# OSSI-1_OBC_3.net
KiCad netlist of a schematic drawn in Altium Designer
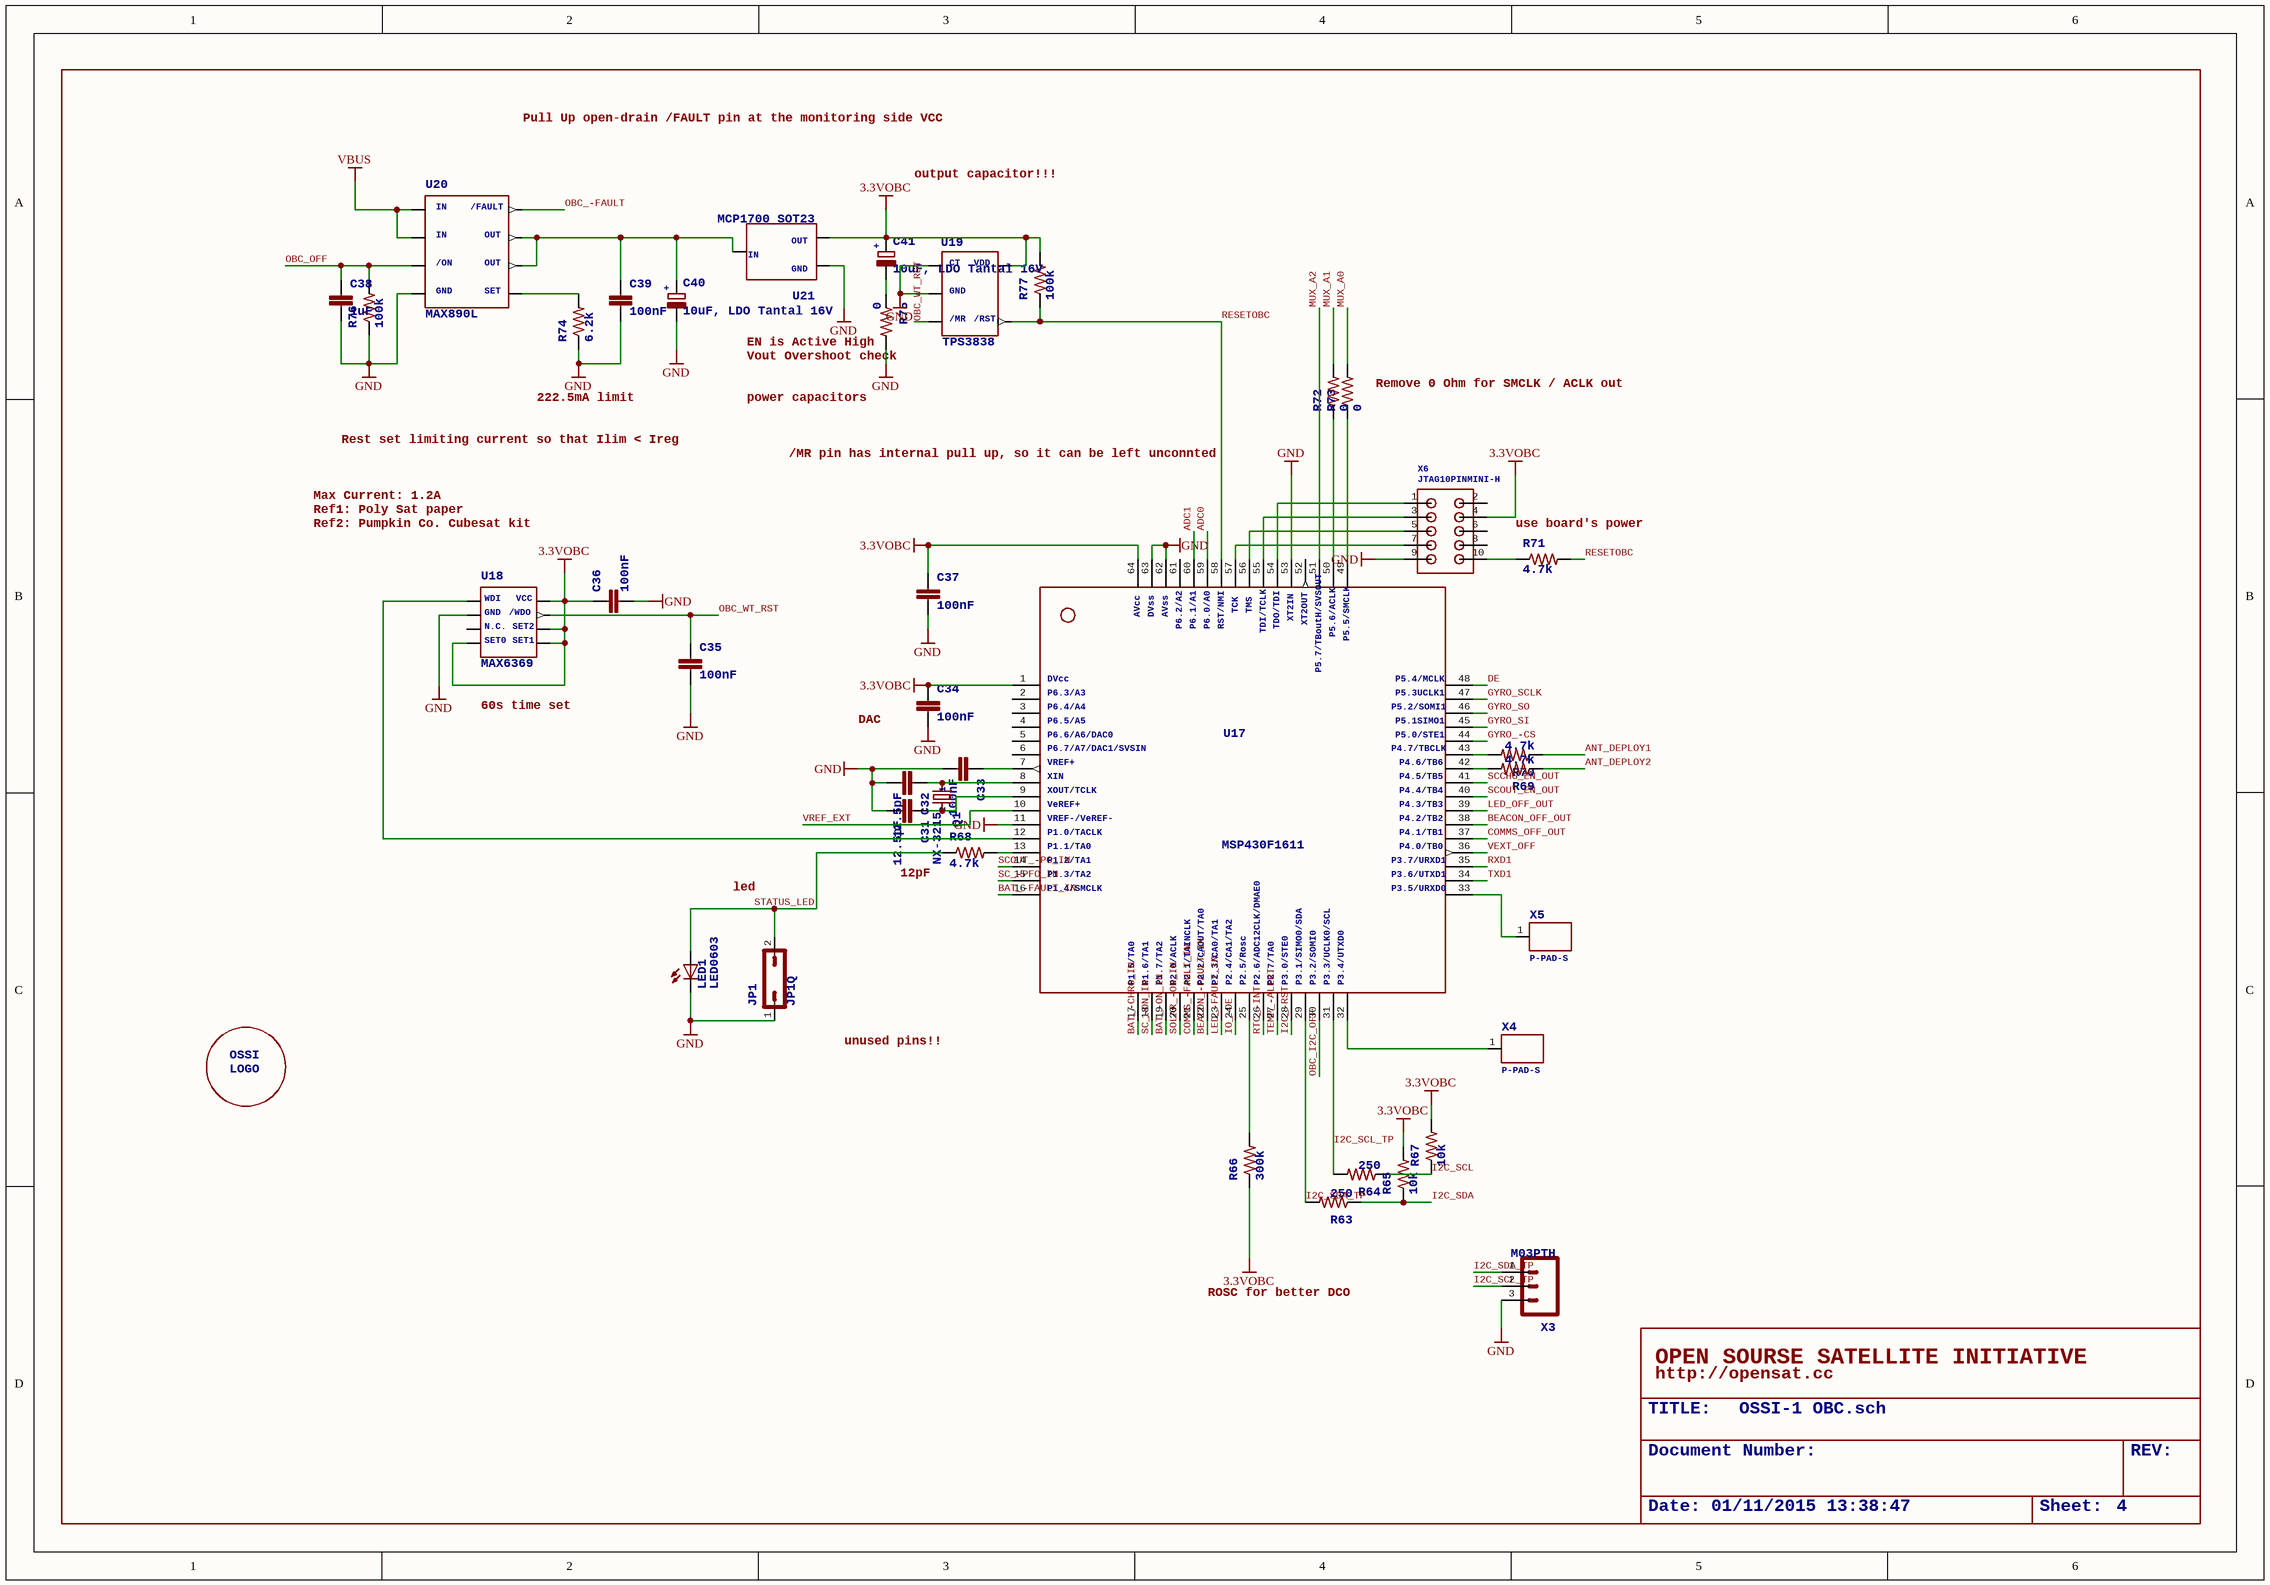
[diagram p0: OSSI-1 OBC_3.SchDoc]

(export (version "E")
  (design (tool "Eeschema 10.0.6"))
  (components
    (comp (ref "C31")
      (value "12.5pF")
      (footprint "C0603(1608)")
      (fields (field (name ">NAME") "C31") (field (name ">VALUE") "12.5pF"))
      (libsource (lib "") (part "C0603(1608)_1"))
    )
    (comp (ref "C32")
      (value "12.5pF")
      (footprint "C0603(1608)")
      (fields (field (name ">NAME") "C32") (field (name ">VALUE") "12.5pF"))
      (libsource (lib "") (part "C0603(1608)_1"))
    )
    (comp (ref "C33")
      (value "100nF")
      (footprint "C0603(1608)")
      (fields (field (name ">NAME") "C33") (field (name ">VALUE") "100nF"))
      (libsource (lib "") (part "C0603(1608)_1"))
    )
    (comp (ref "C34")
      (value "100nF")
      (footprint "C0603(1608)")
      (fields (field (name ">NAME") "C34") (field (name ">VALUE") "100nF"))
      (libsource (lib "") (part "C0603(1608)_2"))
    )
    (comp (ref "C35")
      (value "100nF")
      (footprint "C0603(1608)")
      (fields (field (name ">NAME") "C35") (field (name ">VALUE") "100nF"))
      (libsource (lib "") (part "C0603(1608)_2"))
    )
    (comp (ref "C36")
      (value "100nF")
      (footprint "C0603(1608)")
      (fields (field (name ">NAME") "C36") (field (name ">VALUE") "100nF"))
      (libsource (lib "OSSI") (part "C0603(1608)"))
    )
    (comp (ref "C37")
      (value "100nF")
      (footprint "C0603(1608)")
      (fields (field (name ">NAME") "C37") (field (name ">VALUE") "100nF"))
      (libsource (lib "") (part "C0603(1608)_2"))
    )
    (comp (ref "C38")
      (value "1uF")
      (footprint "C0603(1608)")
      (fields (field (name ">NAME") "C38") (field (name ">VALUE") "1uF"))
      (libsource (lib "") (part "C0603(1608)_2"))
    )
    (comp (ref "C39")
      (value "100nF")
      (footprint "C0603(1608)")
      (fields (field (name ">NAME") "C39") (field (name ">VALUE") "100nF"))
      (libsource (lib "") (part "C0603(1608)_2"))
    )
    (comp (ref "C40")
      (value "10uF, LDO Tantal 16V")
      (footprint "C1206(3216)-A")
      (fields
        (field (name ">NAME") "C40")
        (field (name "+") "+")
        (field (name ">VALUE") "10uF, LDO Tantal 16V")
      )
      (libsource (lib "OSSI") (part "C-TANTAL-A"))
    )
    (comp (ref "C41")
      (value "10uF, LDO Tantal 16V")
      (footprint "C1206(3216)-A")
      (fields
        (field (name ">NAME") "C41")
        (field (name "+") "+")
        (field (name ">VALUE") "10uF, LDO Tantal 16V")
      )
      (libsource (lib "OSSI") (part "C-TANTAL-A"))
    )
    (comp (ref "JP1")
      (value "JP1Q")
      (footprint "JP1")
      (description "<b>JUMPER</b>")
      (fields (field (name ">NAME") "JP1") (field (name ">VALUE") "JP1Q"))
      (libsource (lib "OSSI") (part "JP1Q"))
    )
    (comp (ref "LED1")
      (value "LED0603")
      (footprint "LED-0603")
      (fields (field (name ">NAME") "LED1") (field (name ">VALUE") "LED0603"))
      (libsource (lib "SparkFun") (part "LED0603"))
    )
    (comp (ref "Q1")
      (value "NX-3215")
      (footprint "NX-3215")
      (fields
        (field (name ">NAME") "Q1")
        (field (name ">VALUE") "NX-3215")
        (field (name "1") "1")
        (field (name "2") "2")
      )
      (libsource (lib "OSSI") (part "NX-3215"))
    )
    (comp (ref "R63")
      (value "250")
      (footprint "R0603(1608)")
      (fields (field (name ">NAME") "R63") (field (name ">VALUE") "250"))
      (libsource (lib "OSSI") (part "R0603(1608)"))
    )
    (comp (ref "R64")
      (value "250")
      (footprint "R0603(1608)")
      (fields (field (name ">NAME") "R64") (field (name ">VALUE") "250"))
      (libsource (lib "OSSI") (part "R0603(1608)"))
    )
    (comp (ref "R65")
      (value "10k")
      (footprint "R0603(1608)")
      (fields (field (name ">NAME") "R65") (field (name ">VALUE") "10k"))
      (libsource (lib "OSSI") (part "R0603(1608)"))
    )
    (comp (ref "R66")
      (value "300k")
      (footprint "R0603(1608)")
      (fields (field (name ">NAME") "R66") (field (name ">VALUE") "300k"))
      (libsource (lib "OSSI") (part "R0603(1608)"))
    )
    (comp (ref "R67")
      (value "10k")
      (footprint "R0603(1608)")
      (fields (field (name ">NAME") "R67") (field (name ">VALUE") "10k"))
      (libsource (lib "OSSI") (part "R0603(1608)"))
    )
    (comp (ref "R68")
      (value "4.7k")
      (footprint "R0603(1608)")
      (fields (field (name ">NAME") "R68") (field (name ">VALUE") "4.7k"))
      (libsource (lib "OSSI") (part "R0603(1608)"))
    )
    (comp (ref "R69")
      (value "4.7k")
      (footprint "R0603(1608)")
      (fields (field (name ">NAME") "R69") (field (name ">VALUE") "4.7k"))
      (libsource (lib "OSSI") (part "R0603(1608)"))
    )
    (comp (ref "R70")
      (value "4.7k")
      (footprint "R0603(1608)")
      (fields (field (name ">NAME") "R70") (field (name ">VALUE") "4.7k"))
      (libsource (lib "OSSI") (part "R0603(1608)"))
    )
    (comp (ref "R71")
      (value "4.7k")
      (footprint "R0603(1608)")
      (fields (field (name ">NAME") "R71") (field (name ">VALUE") "4.7k"))
      (libsource (lib "OSSI") (part "R0603(1608)"))
    )
    (comp (ref "R72")
      (value "0")
      (footprint "R0603(1608)")
      (fields (field (name ">NAME") "R72") (field (name ">VALUE") "0"))
      (libsource (lib "OSSI") (part "R0603(1608)"))
    )
    (comp (ref "R73")
      (value "0")
      (footprint "R0603(1608)")
      (fields (field (name ">NAME") "R73") (field (name ">VALUE") "0"))
      (libsource (lib "OSSI") (part "R0603(1608)"))
    )
    (comp (ref "R74")
      (value "6.2k")
      (footprint "R0603(1608)")
      (fields (field (name ">NAME") "R74") (field (name ">VALUE") "6.2k"))
      (libsource (lib "OSSI") (part "R0603(1608)"))
    )
    (comp (ref "R75")
      (value "0")
      (footprint "R0603(1608)")
      (fields (field (name ">NAME") "R75") (field (name ">VALUE") "0"))
      (libsource (lib "OSSI") (part "R0603(1608)"))
    )
    (comp (ref "R76")
      (value "100k")
      (footprint "R0603(1608)")
      (fields (field (name ">NAME") "R76") (field (name ">VALUE") "100k"))
      (libsource (lib "OSSI") (part "R0603(1608)"))
    )
    (comp (ref "R77")
      (value "100k")
      (footprint "R0603(1608)")
      (fields (field (name ">NAME") "R77") (field (name ">VALUE") "100k"))
      (libsource (lib "OSSI") (part "R0603(1608)"))
    )
    (comp (ref "U$1")
      (value "OSSILOGORECT")
      (footprint "OSSILOGORECT1005")
      (fields (field (name "OSSI") "OSSI") (field (name "LOGO") "LOGO"))
      (libsource (lib "OSSI") (part "OSSILOGORECT"))
    )
    (comp (ref "U17")
      (value "MSP430F1611")
      (footprint "PM/PAG64")
      (description "<b>MSP430F1611</b>")
      (fields
        (field (name "AVCC") "AVcc")
        (field (name "DVSS") "DVss")
        (field (name "AVSS") "AVss")
        (field (name "P6.2/A2") "P6.2/A2")
        (field (name "P6.1/A1") "P6.1/A1")
        (field (name "P6.0/A0") "P6.0/A0")
        (field (name "RST/NMI") "RST/NMI")
        (field (name "TCK") "TCK")
        (field (name "TMS") "TMS")
        (field (name "TDI/TCLK") "TDI/TCLK")
        (field (name "TDO/TDI") "TDO/TDI")
        (field (name "XT2IN") "XT2IN")
        (field (name "XT2OUT") "XT2OUT")
        (field (name "P5.7/TBOUTH/SVSOUT") "P5.7/TBoutH/SVSOUT")
        (field (name "P5.6/ACLK") "P5.6/ACLK")
        (field (name "P5.5/SMCLK") "P5.5/SMCLK")
        (field (name "DVCC") "DVcc")
        (field (name "P6.3/A3") "P6.3/A3")
        (field (name "P6.4/A4") "P6.4/A4")
        (field (name "P6.5/A5") "P6.5/A5")
        (field (name "P6.6/A6/DAC0") "P6.6/A6/DAC0")
        (field (name "P6.7/A7/DAC1/SVSIN") "P6.7/A7/DAC1/SVSIN")
        (field (name "VREF+") "VREF+")
        (field (name "XIN") "XIN")
        (field (name "XOUT/TCLK") "XOUT/TCLK")
        (field (name "VEREF+") "VeREF+")
        (field (name "VREF-/VEREF-") "VREF-/VeREF-")
        (field (name "P1.0/TACLK") "P1.0/TACLK")
        (field (name "P1.1/TA0") "P1.1/TA0")
        (field (name "P1.2/TA1") "P1.2/TA1")
        (field (name "P1.3/TA2") "P1.3/TA2")
        (field (name "P1.4/SMCLK") "P1.4/SMCLK")
        (field (name "P1.5/TA0") "P1.5/TA0")
        (field (name "P1.6/TA1") "P1.6/TA1")
        (field (name "P1.7/TA2") "P1.7/TA2")
        (field (name "P2.0/ACLK") "P2.0/ACLK")
        (field (name "P2.1/TAINCLK") "P2.1/TAINCLK")
        (field (name "P2.2/CAOUT/TA0") "P2.2/CAOUT/TA0")
        (field (name "P2.3/CA0/TA1") "P2.3/CA0/TA1")
        (field (name "P2.4/CA1/TA2") "P2.4/CA1/TA2")
        (field (name "P2.5/ROSC") "P2.5/Rosc")
        (field (name "P2.6/ADC12CLK/DMAE0") "P2.6/ADC12CLK/DMAE0")
        (field (name "P2.7/TA0") "P2.7/TA0")
        (field (name "P3.0/STE0") "P3.0/STE0")
        (field (name "P3.1/SIMO0/SDA") "P3.1/SIMO0/SDA")
        (field (name "P3.2/SOMI0") "P3.2/SOMI0")
        (field (name "P3.3/UCLK0/SCL") "P3.3/UCLK0/SCL")
        (field (name "P3.4/UTXD0") "P3.4/UTXD0")
        (field (name "P5.4/MCLK") "P5.4/MCLK")
        (field (name "P5.3UCLK1") "P5.3UCLK1")
        (field (name "P5.2/SOMI1") "P5.2/SOMI1")
        (field (name "P5.1SIMO1") "P5.1SIMO1")
        (field (name "P5.0/STE1") "P5.0/STE1")
        (field (name "P4.7/TBCLK") "P4.7/TBCLK")
        (field (name "P4.6/TB6") "P4.6/TB6")
        (field (name "P4.5/TB5") "P4.5/TB5")
        (field (name "P4.4/TB4") "P4.4/TB4")
        (field (name "P4.3/TB3") "P4.3/TB3")
        (field (name "P4.2/TB2") "P4.2/TB2")
        (field (name "P4.1/TB1") "P4.1/TB1")
        (field (name "P4.0/TB0") "P4.0/TB0")
        (field (name "P3.7/URXD1") "P3.7/URXD1")
        (field (name "P3.6/UTXD1") "P3.6/UTXD1")
        (field (name "P3.5/URXD0") "P3.5/URXD0")
        (field (name ">VALUE") "MSP430F1611")
        (field (name ">NAME") "U17")
      )
      (libsource (lib "OSSI") (part "MSP430F1611"))
    )
    (comp (ref "U18")
      (value "MAX6369")
      (footprint "SOT23-8")
      (fields
        (field (name "WDI") "WDI")
        (field (name "GND") "GND")
        (field (name "N.C.") "N.C.")
        (field (name "SET0") "SET0")
        (field (name "SET1") "SET1")
        (field (name "SET2") "SET2")
        (field (name "/WDO") "/WDO")
        (field (name "VCC") "VCC")
        (field (name ">NAME") "U18")
        (field (name ">VALUE") "MAX6369")
      )
      (libsource (lib "OSSI") (part "MAX6369"))
    )
    (comp (ref "U19")
      (value "TPS3838")
      (footprint "SOT23-5DBV")
      (fields
        (field (name ">NAME") "U19")
        (field (name ">VALUE") "TPS3838")
        (field (name "CT") "CT")
        (field (name "/MR") "/MR")
        (field (name "GND") "GND")
        (field (name "VDD") "VDD")
        (field (name "/RST") "/RST")
      )
      (libsource (lib "OSSI") (part "TPS3838"))
    )
    (comp (ref "U20")
      (value "MAX890L")
      (footprint "SO8")
      (fields
        (field (name "IN") "IN")
        (field (name "IN_1") "IN")
        (field (name "/ON") "/ON")
        (field (name "GND") "GND")
        (field (name "SET") "SET")
        (field (name "OUT") "OUT")
        (field (name "OUT_1") "OUT")
        (field (name "/FAULT") "/FAULT")
        (field (name ">NAME") "U20")
        (field (name ">VALUE") "MAX890L")
      )
      (libsource (lib "OSSI") (part "MAX890L"))
    )
    (comp (ref "U21")
      (value "MCP1700_SOT23")
      (footprint "SOT23")
      (description "MCP1700 LDO from Microchips")
      (fields
        (field (name ">NAME") "U21")
        (field (name ">VALUE") "MCP1700_SOT23")
        (field (name "IN") "IN")
        (field (name "GND") "GND")
        (field (name "OUT") "OUT")
      )
      (libsource (lib "OSSI") (part "MCP1700_SOT23"))
    )
    (comp (ref "X3")
      (value "M03PTH")
      (footprint "1X03")
      (fields (field (name ">VALUE") "M03PTH") (field (name ">NAME") "X3"))
      (libsource (lib "OSSI") (part "M03PTH"))
    )
    (comp (ref "X4")
      (value "P-PAD-S")
      (footprint "P-PAD-S")
      (fields (field (name ">NAME") "X4") (field (name ">VALUE") "P-PAD-S"))
      (libsource (lib "OSSI") (part "P-PAD-S"))
    )
    (comp (ref "X5")
      (value "P-PAD-S")
      (footprint "P-PAD-S")
      (fields (field (name ">NAME") "X5") (field (name ">VALUE") "P-PAD-S"))
      (libsource (lib "OSSI") (part "P-PAD-S"))
    )
    (comp (ref "X6")
      (value "JTAG10PINMINI-H")
      (footprint "M50-3200545")
      (fields (field (name ">NAME") "X6") (field (name ">VALUE") "JTAG10PINMINI-H"))
      (libsource (lib "OSSI") (part "JTAG10PINMINI-H"))
    )
  )
  (nets
    (net (code "1") (name "/ADC0") (class "Default")
      (node (ref "U17") (pin "59") (pinfunction "59_59") (pintype "passive"))
    )
    (net (code "2") (name "/ADC1") (class "Default")
      (node (ref "U17") (pin "60") (pinfunction "60_60") (pintype "passive"))
    )
    (net (code "3") (name "/ANT_DEPLOY1") (class "Default")
      (node (ref "R70") (pin "1") (pinfunction "1_1") (pintype "passive"))
    )
    (net (code "4") (name "/ANT_DEPLOY2") (class "Default")
      (node (ref "R69") (pin "1") (pinfunction "1_1") (pintype "passive"))
    )
    (net (code "5") (name "/BAT_-CHRG_IN") (class "Default")
      (node (ref "U17") (pin "17") (pinfunction "17_17") (pintype "passive"))
    )
    (net (code "6") (name "/BAT_-FAULT_IN") (class "Default")
      (node (ref "U17") (pin "16") (pinfunction "16_16") (pintype "passive"))
    )
    (net (code "7") (name "/BAT_-ON_IN") (class "Default")
      (node (ref "U17") (pin "19") (pinfunction "19_19") (pintype "passive"))
    )
    (net (code "8") (name "/BEACON_-FAULT_IN") (class "Default")
      (node (ref "U17") (pin "22") (pinfunction "22_22") (pintype "passive"))
    )
    (net (code "9") (name "/BEACON_OFF_OUT") (class "Default")
      (node (ref "U17") (pin "38") (pinfunction "38_38") (pintype "passive"))
    )
    (net (code "10") (name "/COMMS_-FAULT_IN") (class "Default")
      (node (ref "U17") (pin "21") (pinfunction "21_21") (pintype "passive"))
    )
    (net (code "11") (name "/COMMS_OFF_OUT") (class "Default")
      (node (ref "U17") (pin "37") (pinfunction "37_37") (pintype "passive"))
    )
    (net (code "12") (name "/DE") (class "Default")
      (node (ref "U17") (pin "48") (pinfunction "48_48") (pintype "passive"))
    )
    (net (code "13") (name "/GYRO_-CS") (class "Default")
      (node (ref "U17") (pin "44") (pinfunction "44_44") (pintype "passive"))
    )
    (net (code "14") (name "/GYRO_SCLK") (class "Default")
      (node (ref "U17") (pin "47") (pinfunction "47_47") (pintype "passive"))
    )
    (net (code "15") (name "/GYRO_SI") (class "Default")
      (node (ref "U17") (pin "45") (pinfunction "45_45") (pintype "passive"))
    )
    (net (code "16") (name "/GYRO_SO") (class "Default")
      (node (ref "U17") (pin "46") (pinfunction "46_46") (pintype "passive"))
    )
    (net (code "17") (name "/I2C_-RST") (class "Default")
      (node (ref "U17") (pin "28") (pinfunction "28_28") (pintype "passive"))
    )
    (net (code "18") (name "/I2C_SCL") (class "Default")
      (node (ref "R64") (pin "1") (pinfunction "1_1") (pintype "passive"))
      (node (ref "R67") (pin "1") (pinfunction "1_1") (pintype "passive"))
    )
    (net (code "19") (name "/I2C_SCL_TP") (class "Default")
      (node (ref "R64") (pin "2") (pinfunction "2_2") (pintype "passive"))
      (node (ref "U17") (pin "31") (pinfunction "31_31") (pintype "passive"))
      (node (ref "X3") (pin "2") (pinfunction "2_2") (pintype "passive"))
    )
    (net (code "20") (name "/I2C_SDA") (class "Default")
      (node (ref "R63") (pin "1") (pinfunction "1_1") (pintype "passive"))
      (node (ref "R65") (pin "1") (pinfunction "1_1") (pintype "passive"))
    )
    (net (code "21") (name "/I2C_SDA_TP") (class "Default")
      (node (ref "R63") (pin "2") (pinfunction "2_2") (pintype "passive"))
      (node (ref "U17") (pin "29") (pinfunction "29_29") (pintype "passive"))
      (node (ref "X3") (pin "1") (pinfunction "1_1") (pintype "passive"))
    )
    (net (code "22") (name "/IO_-OE") (class "Default")
      (node (ref "U17") (pin "24") (pinfunction "24_24") (pintype "passive"))
    )
    (net (code "23") (name "/LED_-FAULT_IN") (class "Default")
      (node (ref "U17") (pin "23") (pinfunction "23_23") (pintype "passive"))
    )
    (net (code "24") (name "/LED_OFF_OUT") (class "Default")
      (node (ref "U17") (pin "39") (pinfunction "39_39") (pintype "passive"))
    )
    (net (code "25") (name "/MUX_A0") (class "Default")
      (node (ref "R73") (pin "2") (pinfunction "2_2") (pintype "passive"))
    )
    (net (code "26") (name "/MUX_A1") (class "Default")
      (node (ref "R72") (pin "2") (pinfunction "2_2") (pintype "passive"))
    )
    (net (code "27") (name "/MUX_A2") (class "Default")
      (node (ref "U17") (pin "51") (pinfunction "51_51") (pintype "passive"))
    )
    (net (code "28") (name "/OBC_-FAULT") (class "Default")
      (node (ref "U20") (pin "8") (pinfunction "P$8_8") (pintype "output"))
    )
    (net (code "29") (name "/OBC_I2C_OFF") (class "Default")
      (node (ref "U17") (pin "30") (pinfunction "30_30") (pintype "passive"))
    )
    (net (code "30") (name "/OBC_OFF") (class "Default")
      (node (ref "C38") (pin "1") (pinfunction "1_1") (pintype "passive"))
      (node (ref "R76") (pin "2") (pinfunction "2_2") (pintype "passive"))
      (node (ref "U20") (pin "3") (pinfunction "P$3_3") (pintype "passive"))
    )
    (net (code "31") (name "/OBC_WT_RST") (class "Default")
      (node (ref "C35") (pin "1") (pinfunction "1_1") (pintype "passive"))
      (node (ref "U18") (pin "7") (pinfunction "P$7_7") (pintype "output"))
      (node (ref "U19") (pin "3") (pinfunction "P$3_3") (pintype "passive"))
    )
    (net (code "32") (name "/RESETOBC") (class "Default")
      (node (ref "R71") (pin "2") (pinfunction "2_2") (pintype "passive"))
      (node (ref "R77") (pin "1") (pinfunction "1_1") (pintype "passive"))
      (node (ref "U17") (pin "58") (pinfunction "58_58") (pintype "passive"))
      (node (ref "U19") (pin "4") (pinfunction "P$4_4") (pintype "output"))
    )
    (net (code "33") (name "/RTC_-INT") (class "Default")
      (node (ref "U17") (pin "26") (pinfunction "26_26") (pintype "passive"))
    )
    (net (code "34") (name "/RXD1") (class "Default")
      (node (ref "U17") (pin "35") (pinfunction "35_35") (pintype "passive"))
    )
    (net (code "35") (name "/SCCHG_EN_OUT") (class "Default")
      (node (ref "U17") (pin "41") (pinfunction "41_41") (pintype "passive"))
    )
    (net (code "36") (name "/SCOUT_-PG_IN") (class "Default")
      (node (ref "U17") (pin "14") (pinfunction "14_14") (pintype "passive"))
    )
    (net (code "37") (name "/SCOUT_EN_OUT") (class "Default")
      (node (ref "U17") (pin "40") (pinfunction "40_40") (pintype "passive"))
    )
    (net (code "38") (name "/SC_-ON_IN") (class "Default")
      (node (ref "U17") (pin "18") (pinfunction "18_18") (pintype "passive"))
    )
    (net (code "39") (name "/SC_-PFO_IN") (class "Default")
      (node (ref "U17") (pin "15") (pinfunction "15_15") (pintype "passive"))
    )
    (net (code "40") (name "/SOLAR_-ON_IN") (class "Default")
      (node (ref "U17") (pin "20") (pinfunction "20_20") (pintype "passive"))
    )
    (net (code "41") (name "/STATUS_LED") (class "Default")
      (node (ref "JP1") (pin "2") (pinfunction "2_2") (pintype "passive"))
      (node (ref "LED1") (pin "A") (pinfunction "A_A") (pintype "passive"))
      (node (ref "R68") (pin "1") (pinfunction "1_1") (pintype "passive"))
    )
    (net (code "42") (name "/TEMP_-ALERT") (class "Default")
      (node (ref "U17") (pin "27") (pinfunction "27_27") (pintype "passive"))
    )
    (net (code "43") (name "/TXD1") (class "Default")
      (node (ref "U17") (pin "34") (pinfunction "34_34") (pintype "passive"))
    )
    (net (code "44") (name "/VEXT_OFF") (class "Default")
      (node (ref "U17") (pin "36") (pinfunction "36_36") (pintype "output"))
    )
    (net (code "45") (name "/VREF_EXT") (class "Default")
      (node (ref "U17") (pin "10") (pinfunction "10_10") (pintype "passive"))
    )
    (net (code "46") (name "3.3VOBC") (class "Default")
      (node (ref "C34") (pin "1") (pinfunction "1_1") (pintype "passive"))
      (node (ref "C36") (pin "1") (pinfunction "1_1") (pintype "passive"))
      (node (ref "C37") (pin "1") (pinfunction "1_1") (pintype "passive"))
      (node (ref "C41") (pin "1") (pinfunction "+_1") (pintype "passive"))
      (node (ref "R65") (pin "2") (pinfunction "2_2") (pintype "passive"))
      (node (ref "R66") (pin "1") (pinfunction "1_1") (pintype "passive"))
      (node (ref "R67") (pin "2") (pinfunction "2_2") (pintype "passive"))
      (node (ref "R77") (pin "2") (pinfunction "2_2") (pintype "passive"))
      (node (ref "U17") (pin "1") (pinfunction "1_1") (pintype "power_in"))
      (node (ref "U17") (pin "64") (pinfunction "64_64") (pintype "power_in"))
      (node (ref "U18") (pin "4") (pinfunction "P$4_4") (pintype "passive"))
      (node (ref "U18") (pin "5") (pinfunction "P$5_5") (pintype "passive"))
      (node (ref "U18") (pin "6") (pinfunction "P$6_6") (pintype "passive"))
      (node (ref "U18") (pin "8") (pinfunction "P$8_8") (pintype "power_in"))
      (node (ref "U19") (pin "5") (pinfunction "P$5_5") (pintype "power_in"))
      (node (ref "U21") (pin "2") (pinfunction "2_2") (pintype "power_in"))
      (node (ref "X6") (pin "4") (pinfunction "4_4") (pintype "passive"))
    )
    (net (code "47") (name "GND") (class "Default")
      (node (ref "C31") (pin "2") (pinfunction "2_2") (pintype "passive"))
      (node (ref "C32") (pin "2") (pinfunction "2_2") (pintype "passive"))
      (node (ref "C33") (pin "2") (pinfunction "2_2") (pintype "passive"))
      (node (ref "C34") (pin "2") (pinfunction "2_2") (pintype "passive"))
      (node (ref "C35") (pin "2") (pinfunction "2_2") (pintype "passive"))
      (node (ref "C36") (pin "2") (pinfunction "2_2") (pintype "passive"))
      (node (ref "C37") (pin "2") (pinfunction "2_2") (pintype "passive"))
      (node (ref "C38") (pin "2") (pinfunction "2_2") (pintype "passive"))
      (node (ref "C39") (pin "2") (pinfunction "2_2") (pintype "passive"))
      (node (ref "C40") (pin "2") (pinfunction "-_2") (pintype "passive"))
      (node (ref "JP1") (pin "1") (pinfunction "1_1") (pintype "passive"))
      (node (ref "LED1") (pin "C") (pinfunction "C_C") (pintype "passive"))
      (node (ref "R74") (pin "1") (pinfunction "1_1") (pintype "passive"))
      (node (ref "R75") (pin "2") (pinfunction "2_2") (pintype "passive"))
      (node (ref "R76") (pin "1") (pinfunction "1_1") (pintype "passive"))
      (node (ref "U17") (pin "11") (pinfunction "11_11") (pintype "passive"))
      (node (ref "U17") (pin "53") (pinfunction "53_53") (pintype "passive"))
      (node (ref "U17") (pin "62") (pinfunction "62_62") (pintype "power_in"))
      (node (ref "U17") (pin "63") (pinfunction "63_63") (pintype "power_in"))
      (node (ref "U18") (pin "2") (pinfunction "P$2_2") (pintype "power_in"))
      (node (ref "U19") (pin "1") (pinfunction "P$1_1") (pintype "passive"))
      (node (ref "U19") (pin "2") (pinfunction "P$2_2") (pintype "power_in"))
      (node (ref "U20") (pin "4") (pinfunction "P$4_4") (pintype "power_in"))
      (node (ref "U21") (pin "1") (pinfunction "1_1") (pintype "power_in"))
      (node (ref "X3") (pin "3") (pinfunction "3_3") (pintype "passive"))
      (node (ref "X6") (pin "9") (pinfunction "9_9") (pintype "passive"))
    )
    (net (code "48") (name "Net-(C31-Pad1)") (class "Default")
      (node (ref "C31") (pin "1") (pinfunction "1_1") (pintype "passive"))
      (node (ref "Q1") (pin "2") (pinfunction "2_2") (pintype "passive"))
      (node (ref "U17") (pin "9") (pinfunction "9_9") (pintype "passive"))
    )
    (net (code "49") (name "Net-(C32-Pad1)") (class "Default")
      (node (ref "C32") (pin "1") (pinfunction "1_1") (pintype "passive"))
      (node (ref "Q1") (pin "1") (pinfunction "1_1") (pintype "passive"))
      (node (ref "U17") (pin "8") (pinfunction "8_8") (pintype "passive"))
    )
    (net (code "50") (name "Net-(C33-Pad1)") (class "Default")
      (node (ref "C33") (pin "1") (pinfunction "1_1") (pintype "passive"))
      (node (ref "U17") (pin "7") (pinfunction "7_7") (pintype "output"))
    )
    (net (code "51") (name "Net-(C40-+)") (class "Default")
      (node (ref "C39") (pin "1") (pinfunction "1_1") (pintype "passive"))
      (node (ref "C40") (pin "1") (pinfunction "+_1") (pintype "passive"))
      (node (ref "U20") (pin "6") (pinfunction "P$6_6") (pintype "output"))
      (node (ref "U20") (pin "7") (pinfunction "P$7_7") (pintype "output"))
      (node (ref "U21") (pin "3") (pinfunction "3_3") (pintype "power_in"))
    )
    (net (code "52") (name "Net-(C41--)") (class "Default")
      (node (ref "C41") (pin "2") (pinfunction "-_2") (pintype "passive"))
      (node (ref "R75") (pin "1") (pinfunction "1_1") (pintype "passive"))
    )
    (net (code "53") (name "Net-(R66-Pad2)") (class "Default")
      (node (ref "R66") (pin "2") (pinfunction "2_2") (pintype "passive"))
      (node (ref "U17") (pin "25") (pinfunction "25_25") (pintype "passive"))
    )
    (net (code "54") (name "Net-(R68-Pad2)") (class "Default")
      (node (ref "R68") (pin "2") (pinfunction "2_2") (pintype "passive"))
      (node (ref "U17") (pin "13") (pinfunction "13_13") (pintype "passive"))
    )
    (net (code "55") (name "Net-(R69-Pad2)") (class "Default")
      (node (ref "R69") (pin "2") (pinfunction "2_2") (pintype "passive"))
      (node (ref "U17") (pin "42") (pinfunction "42_42") (pintype "passive"))
    )
    (net (code "56") (name "Net-(R70-Pad2)") (class "Default")
      (node (ref "R70") (pin "2") (pinfunction "2_2") (pintype "passive"))
      (node (ref "U17") (pin "43") (pinfunction "43_43") (pintype "passive"))
    )
    (net (code "57") (name "Net-(R71-Pad1)") (class "Default")
      (node (ref "R71") (pin "1") (pinfunction "1_1") (pintype "passive"))
      (node (ref "X6") (pin "10") (pinfunction "10_10") (pintype "passive"))
    )
    (net (code "58") (name "Net-(R72-Pad1)") (class "Default")
      (node (ref "R72") (pin "1") (pinfunction "1_1") (pintype "passive"))
      (node (ref "U17") (pin "50") (pinfunction "50_50") (pintype "passive"))
    )
    (net (code "59") (name "Net-(R73-Pad1)") (class "Default")
      (node (ref "R73") (pin "1") (pinfunction "1_1") (pintype "passive"))
      (node (ref "U17") (pin "49") (pinfunction "49_49") (pintype "passive"))
    )
    (net (code "60") (name "Net-(U17-Pad54)") (class "Default")
      (node (ref "U17") (pin "54") (pinfunction "54_54") (pintype "passive"))
      (node (ref "X6") (pin "1") (pinfunction "1_1") (pintype "passive"))
    )
    (net (code "61") (name "Net-(U17-Pad55)") (class "Default")
      (node (ref "U17") (pin "55") (pinfunction "55_55") (pintype "passive"))
      (node (ref "X6") (pin "3") (pinfunction "3_3") (pintype "passive"))
    )
    (net (code "62") (name "Net-(U17-Pad56)") (class "Default")
      (node (ref "U17") (pin "56") (pinfunction "56_56") (pintype "passive"))
      (node (ref "X6") (pin "5") (pinfunction "5_5") (pintype "passive"))
    )
    (net (code "63") (name "Net-(U17-Pad57)") (class "Default")
      (node (ref "U17") (pin "57") (pinfunction "57_57") (pintype "passive"))
      (node (ref "X6") (pin "7") (pinfunction "7_7") (pintype "passive"))
    )
    (net (code "64") (name "Net-(U18-P$1)") (class "Default")
      (node (ref "U17") (pin "12") (pinfunction "12_12") (pintype "passive"))
      (node (ref "U18") (pin "1") (pinfunction "P$1_1") (pintype "passive"))
    )
    (net (code "65") (name "Net-(U20-P$5)") (class "Default")
      (node (ref "R74") (pin "2") (pinfunction "2_2") (pintype "passive"))
      (node (ref "U20") (pin "5") (pinfunction "P$5_5") (pintype "passive"))
    )
    (net (code "66") (name "Net-(X4-P$1)") (class "Default")
      (node (ref "U17") (pin "32") (pinfunction "32_32") (pintype "passive"))
      (node (ref "X4") (pin "1") (pinfunction "P$1_1") (pintype "passive"))
    )
    (net (code "67") (name "Net-(X5-P$1)") (class "Default")
      (node (ref "U17") (pin "33") (pinfunction "33_33") (pintype "passive"))
      (node (ref "X5") (pin "1") (pinfunction "P$1_1") (pintype "passive"))
    )
    (net (code "68") (name "VBUS") (class "Default")
      (node (ref "U20") (pin "1") (pinfunction "P$1_1") (pintype "passive"))
      (node (ref "U20") (pin "2") (pinfunction "P$2_2") (pintype "passive"))
    )
    (net (code "69") (name "unconnected-(U17-Pad2)") (class "Default")
      (node (ref "U17") (pin "2") (pinfunction "2_2") (pintype "passive"))
    )
    (net (code "70") (name "unconnected-(U17-Pad3)") (class "Default")
      (node (ref "U17") (pin "3") (pinfunction "3_3") (pintype "passive"))
    )
    (net (code "71") (name "unconnected-(U17-Pad4)") (class "Default")
      (node (ref "U17") (pin "4") (pinfunction "4_4") (pintype "passive"))
    )
    (net (code "72") (name "unconnected-(U17-Pad5)") (class "Default")
      (node (ref "U17") (pin "5") (pinfunction "5_5") (pintype "passive"))
    )
    (net (code "73") (name "unconnected-(U17-Pad6)") (class "Default")
      (node (ref "U17") (pin "6") (pinfunction "6_6") (pintype "passive"))
    )
    (net (code "74") (name "unconnected-(U17-Pad52)") (class "Default")
      (node (ref "U17") (pin "52") (pinfunction "52_52") (pintype "output"))
    )
    (net (code "75") (name "unconnected-(U17-Pad61)") (class "Default")
      (node (ref "U17") (pin "61") (pinfunction "61_61") (pintype "passive"))
    )
    (net (code "76") (name "unconnected-(U18-P$3-Pad3)") (class "Default")
      (node (ref "U18") (pin "3") (pinfunction "P$3_3") (pintype "passive"))
    )
    (net (code "77") (name "unconnected-(X6-Pad2)") (class "Default")
      (node (ref "X6") (pin "2") (pinfunction "2_2") (pintype "passive"))
    )
    (net (code "78") (name "unconnected-(X6-Pad6)") (class "Default")
      (node (ref "X6") (pin "6") (pinfunction "6_6") (pintype "passive"))
    )
    (net (code "79") (name "unconnected-(X6-Pad8)") (class "Default")
      (node (ref "X6") (pin "8") (pinfunction "8_8") (pintype "passive"))
    )
  )
)
